# l293d.net
KiCad netlist of a schematic drawn in EAGLE
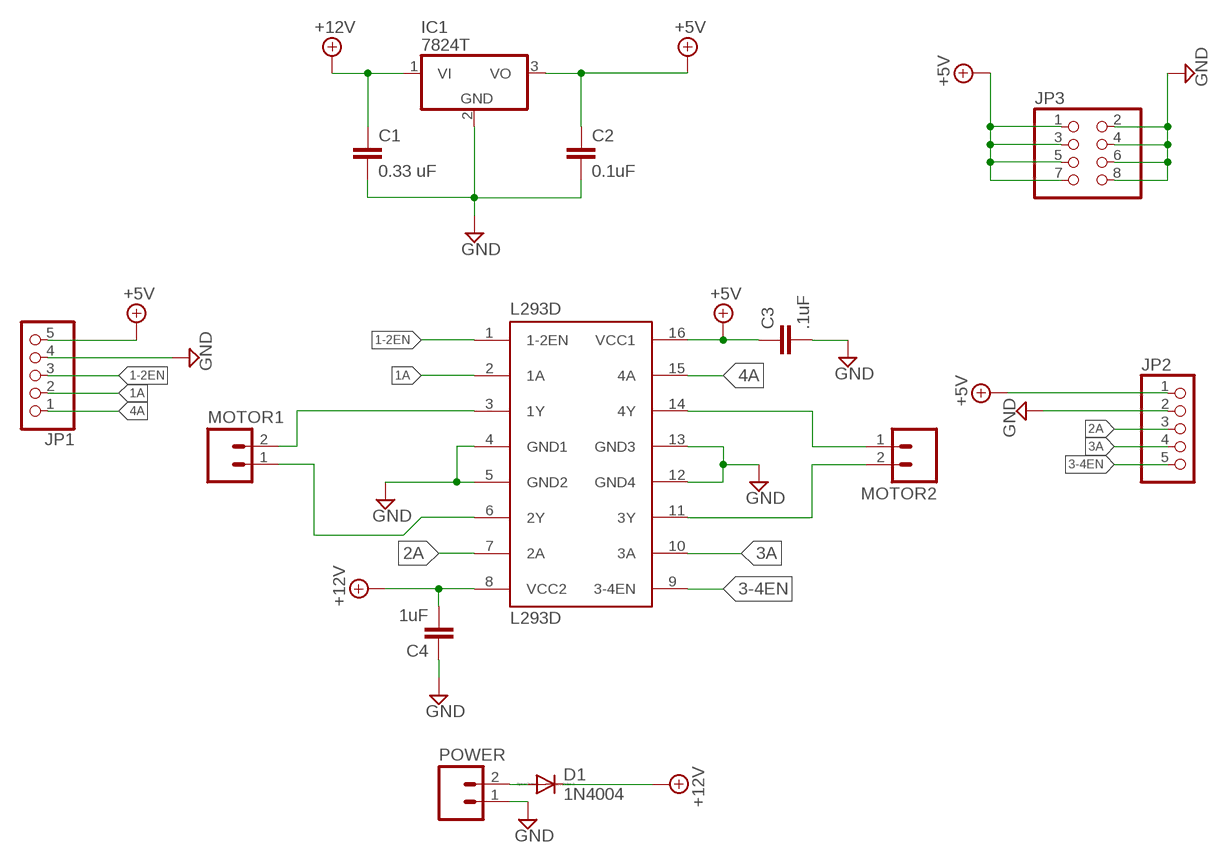
[diagram p0: schematic, sheet 1]

(export (version "E")
  (design (tool "Eeschema 10.0.6"))
  (components
    (comp (ref "C1")
      (value "0.33 uF")
      (footprint "eagle-import:C050-024X044")
      (libsource (lib "eagle-import") (part "C-EU050-024X044"))
    )
    (comp (ref "C2")
      (value "0.1uF")
      (footprint "eagle-import:C050-024X044")
      (libsource (lib "eagle-import") (part "C-EU050-024X044"))
    )
    (comp (ref "C3")
      (value ".1uF")
      (footprint "eagle-import:C050-024X044")
      (libsource (lib "eagle-import") (part "C-EU050-024X044"))
    )
    (comp (ref "C4")
      (value "1uF")
      (footprint "eagle-import:C050-024X044")
      (libsource (lib "eagle-import") (part "C-EU050-024X044"))
    )
    (comp (ref "D1")
      (value "1N4004")
      (footprint "eagle-import:DO41-10")
      (libsource (lib "eagle-import") (part "1N4004"))
    )
    (comp (ref "IC1")
      (value "7824T")
      (footprint "eagle-import:TO220H")
      (libsource (lib "eagle-import") (part "78T24"))
    )
    (comp (ref "JP1")
      (value "PINHD-1X5")
      (footprint "eagle-import:1X05")
      (libsource (lib "eagle-import") (part "PINHD-1X5"))
    )
    (comp (ref "JP2")
      (value "PINHD-1X5")
      (footprint "eagle-import:1X05")
      (libsource (lib "eagle-import") (part "PINHD-1X5"))
    )
    (comp (ref "JP3")
      (value "PINHD-2X4")
      (footprint "eagle-import:2X04")
      (libsource (lib "eagle-import") (part "PINHD-2X4"))
    )
    (comp (ref "L293D")
      (value "L293D")
      (footprint "eagle-import:DIL16")
      (libsource (lib "eagle-import") (part "L293D"))
    )
    (comp (ref "MOTOR1")
      (value "M023.5MM-NO_SILK")
      (footprint "eagle-import:SCREWTERMINAL-3.5MM-2-NS")
      (libsource (lib "eagle-import") (part "M023.5MM-NO_SILK"))
    )
    (comp (ref "MOTOR2")
      (value "M023.5MM-NO_SILK")
      (footprint "eagle-import:SCREWTERMINAL-3.5MM-2-NS")
      (libsource (lib "eagle-import") (part "M023.5MM-NO_SILK"))
    )
    (comp (ref "POWER")
      (value "M023.5MM-NO_SILK")
      (footprint "eagle-import:SCREWTERMINAL-3.5MM-2-NS")
      (libsource (lib "eagle-import") (part "M023.5MM-NO_SILK"))
    )
  )
  (nets
    (net (code "1") (name "+5V") (class "Default")
      (node (ref "C2") (pin "1") (pinfunction "1_1") (pintype "passive"))
      (node (ref "C3") (pin "1") (pinfunction "1_1") (pintype "passive"))
      (node (ref "IC1") (pin "3") (pinfunction "VO_3") (pintype "passive"))
      (node (ref "JP1") (pin "5") (pinfunction "5_5") (pintype "passive"))
      (node (ref "JP2") (pin "1") (pinfunction "1_1") (pintype "passive"))
      (node (ref "JP3") (pin "1") (pinfunction "1_1") (pintype "passive"))
      (node (ref "JP3") (pin "3") (pinfunction "3_3") (pintype "passive"))
      (node (ref "JP3") (pin "5") (pinfunction "5_5") (pintype "passive"))
      (node (ref "JP3") (pin "7") (pinfunction "7_7") (pintype "passive"))
      (node (ref "L293D") (pin "16") (pinfunction "VCC1_16") (pintype "power_in"))
    )
    (net (code "2") (name "+12V") (class "Default")
      (node (ref "C1") (pin "1") (pinfunction "1_1") (pintype "passive"))
      (node (ref "C4") (pin "2") (pinfunction "2_2") (pintype "passive"))
      (node (ref "D1") (pin "C") (pinfunction "C_C") (pintype "passive"))
      (node (ref "IC1") (pin "1") (pinfunction "VI_1") (pintype "input"))
      (node (ref "L293D") (pin "8") (pinfunction "VCC2_8") (pintype "power_in"))
    )
    (net (code "3") (name "1-2EN") (class "Default")
      (node (ref "JP1") (pin "3") (pinfunction "3_3") (pintype "passive"))
      (node (ref "L293D") (pin "1") (pinfunction "1-2EN_1") (pintype "input"))
    )
    (net (code "4") (name "1A") (class "Default")
      (node (ref "JP1") (pin "2") (pinfunction "2_2") (pintype "passive"))
      (node (ref "L293D") (pin "2") (pinfunction "1A_2") (pintype "input"))
    )
    (net (code "5") (name "2A") (class "Default")
      (node (ref "JP2") (pin "3") (pinfunction "3_3") (pintype "passive"))
      (node (ref "L293D") (pin "7") (pinfunction "2A_7") (pintype "input"))
    )
    (net (code "6") (name "3-4EN") (class "Default")
      (node (ref "JP2") (pin "5") (pinfunction "5_5") (pintype "passive"))
      (node (ref "L293D") (pin "9") (pinfunction "3-4EN_9") (pintype "input"))
    )
    (net (code "7") (name "3A") (class "Default")
      (node (ref "JP2") (pin "4") (pinfunction "4_4") (pintype "passive"))
      (node (ref "L293D") (pin "10") (pinfunction "3A_10") (pintype "input"))
    )
    (net (code "8") (name "4A") (class "Default")
      (node (ref "JP1") (pin "1") (pinfunction "1_1") (pintype "passive"))
      (node (ref "L293D") (pin "15") (pinfunction "4A_15") (pintype "input"))
    )
    (net (code "9") (name "GND") (class "Default")
      (node (ref "C1") (pin "2") (pinfunction "2_2") (pintype "passive"))
      (node (ref "C2") (pin "2") (pinfunction "2_2") (pintype "passive"))
      (node (ref "C3") (pin "2") (pinfunction "2_2") (pintype "passive"))
      (node (ref "C4") (pin "1") (pinfunction "1_1") (pintype "passive"))
      (node (ref "IC1") (pin "2") (pinfunction "GND_2") (pintype "passive"))
      (node (ref "JP1") (pin "4") (pinfunction "4_4") (pintype "passive"))
      (node (ref "JP2") (pin "2") (pinfunction "2_2") (pintype "passive"))
      (node (ref "JP3") (pin "2") (pinfunction "2_2") (pintype "passive"))
      (node (ref "JP3") (pin "4") (pinfunction "4_4") (pintype "passive"))
      (node (ref "JP3") (pin "6") (pinfunction "6_6") (pintype "passive"))
      (node (ref "JP3") (pin "8") (pinfunction "8_8") (pintype "passive"))
      (node (ref "L293D") (pin "12") (pinfunction "GND4_12") (pintype "power_in"))
      (node (ref "L293D") (pin "13") (pinfunction "GND3_13") (pintype "power_in"))
      (node (ref "L293D") (pin "4") (pinfunction "GND1_4") (pintype "power_in"))
      (node (ref "L293D") (pin "5") (pinfunction "GND2_5") (pintype "power_in"))
      (node (ref "POWER") (pin "1") (pinfunction "1_1") (pintype "passive"))
    )
    (net (code "10") (name "Net-(D1-PadA)") (class "Default")
      (node (ref "D1") (pin "A") (pinfunction "A_A") (pintype "passive"))
      (node (ref "POWER") (pin "2") (pinfunction "2_2") (pintype "passive"))
    )
    (net (code "11") (name "Net-(L293D-1Y)") (class "Default")
      (node (ref "L293D") (pin "3") (pinfunction "1Y_3") (pintype "output"))
      (node (ref "MOTOR1") (pin "2") (pinfunction "2_2") (pintype "passive"))
    )
    (net (code "12") (name "Net-(L293D-2Y)") (class "Default")
      (node (ref "L293D") (pin "6") (pinfunction "2Y_6") (pintype "output"))
      (node (ref "MOTOR1") (pin "1") (pinfunction "1_1") (pintype "passive"))
    )
    (net (code "13") (name "Net-(L293D-3Y)") (class "Default")
      (node (ref "L293D") (pin "11") (pinfunction "3Y_11") (pintype "output"))
      (node (ref "MOTOR2") (pin "2") (pinfunction "2_2") (pintype "passive"))
    )
    (net (code "14") (name "Net-(L293D-4Y)") (class "Default")
      (node (ref "L293D") (pin "14") (pinfunction "4Y_14") (pintype "output"))
      (node (ref "MOTOR2") (pin "1") (pinfunction "1_1") (pintype "passive"))
    )
  )
)
